# S_M_v4_1_Board.net
KiCad netlist of a schematic drawn in EAGLE
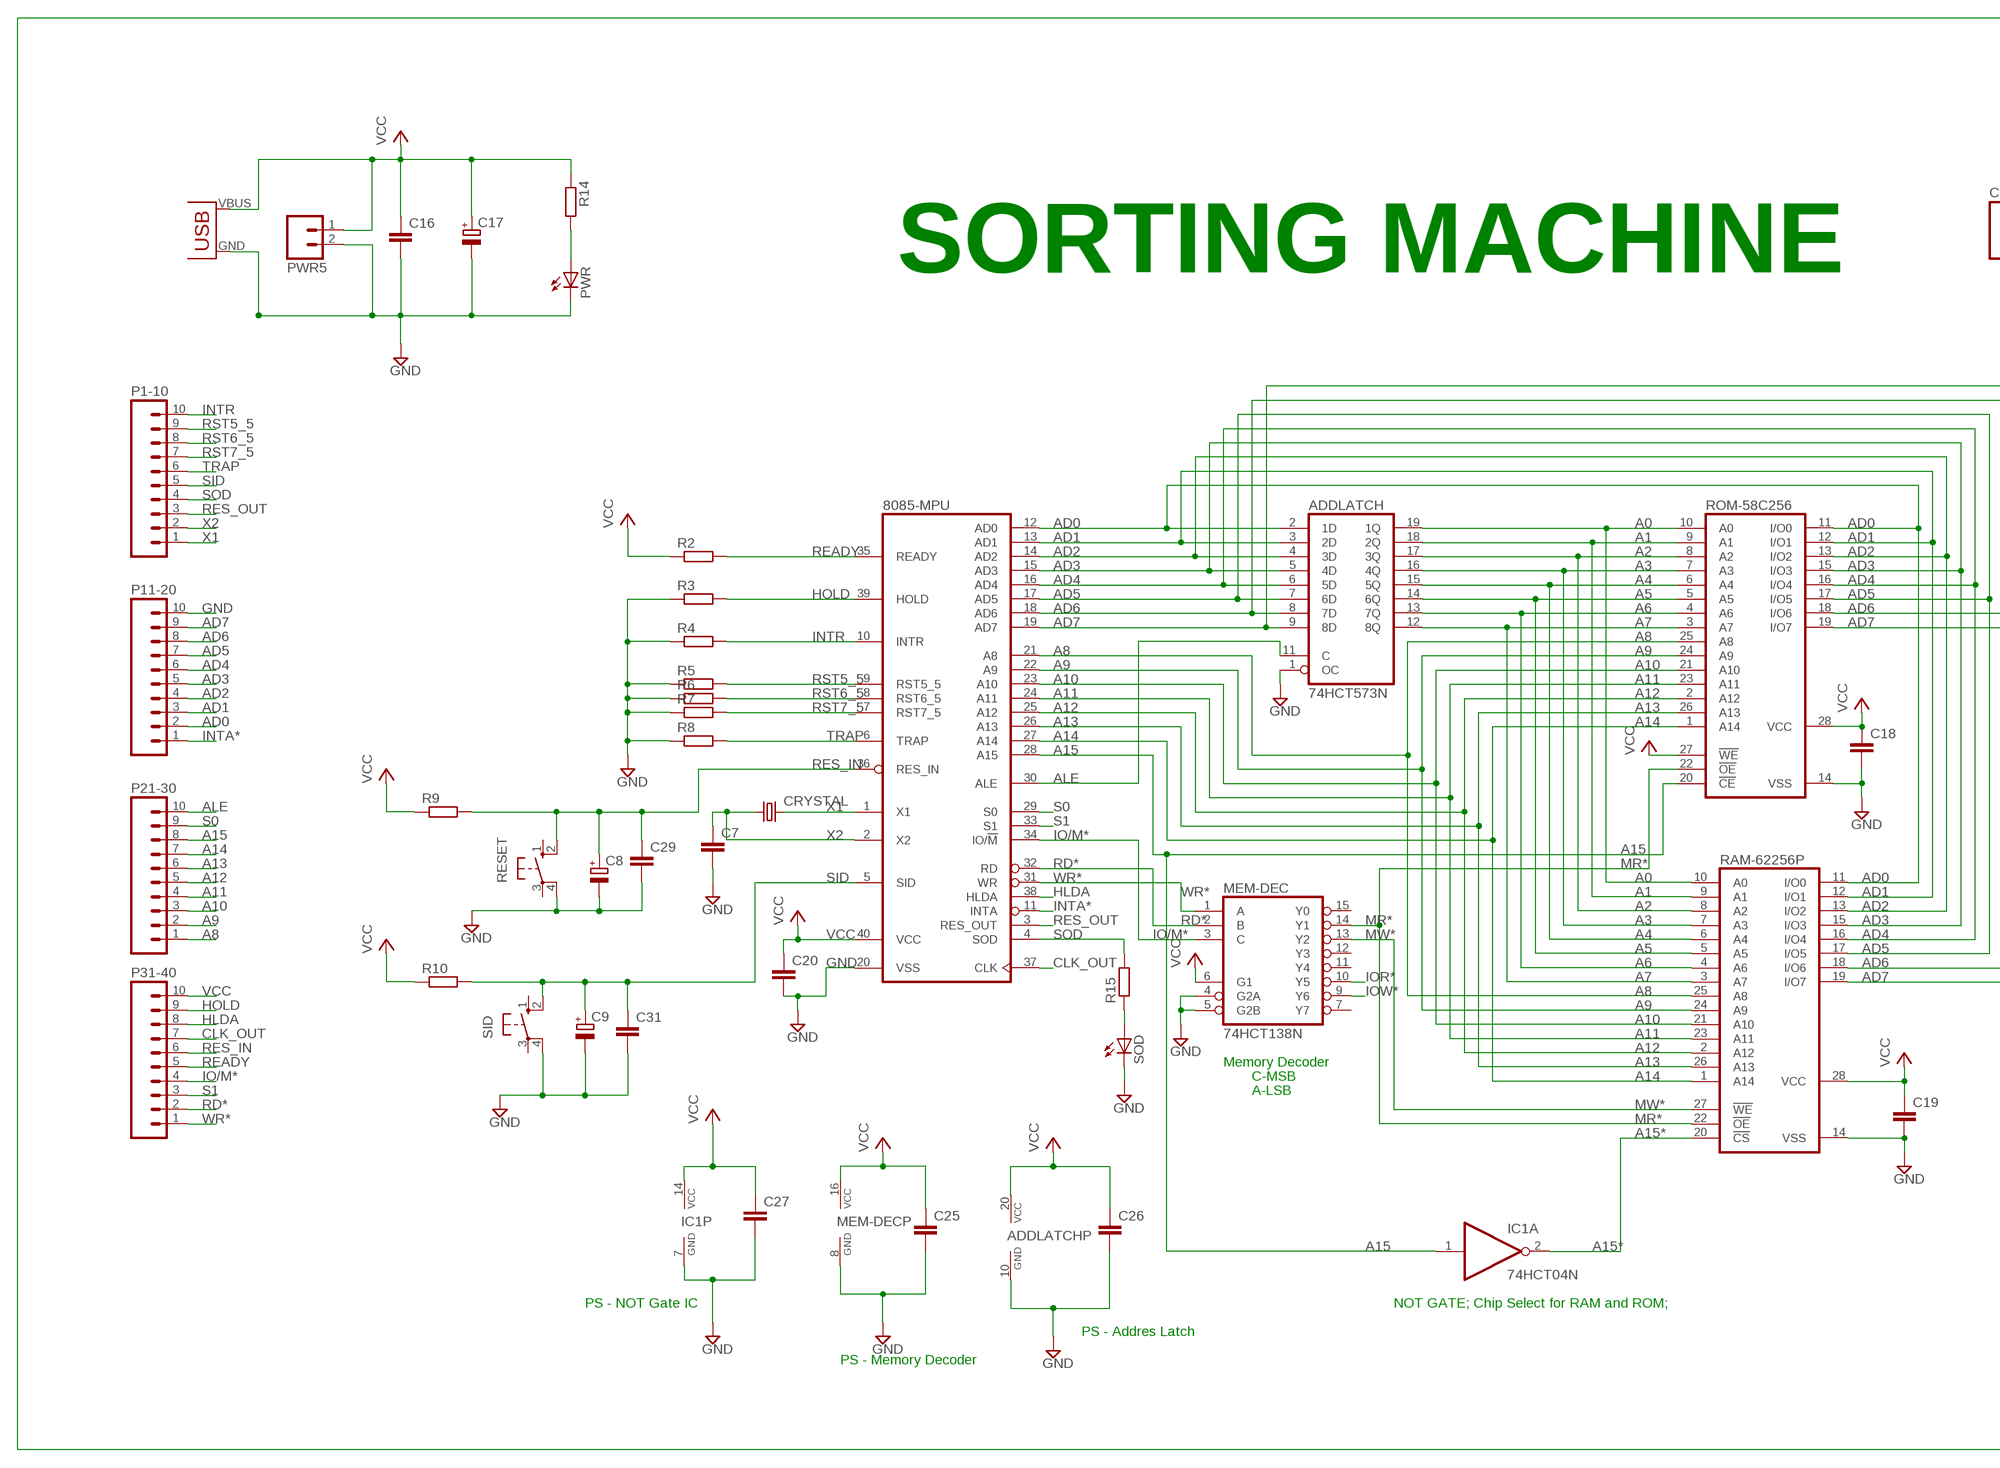
[diagram p0: schematic, sheet 1, part 1 of 2]
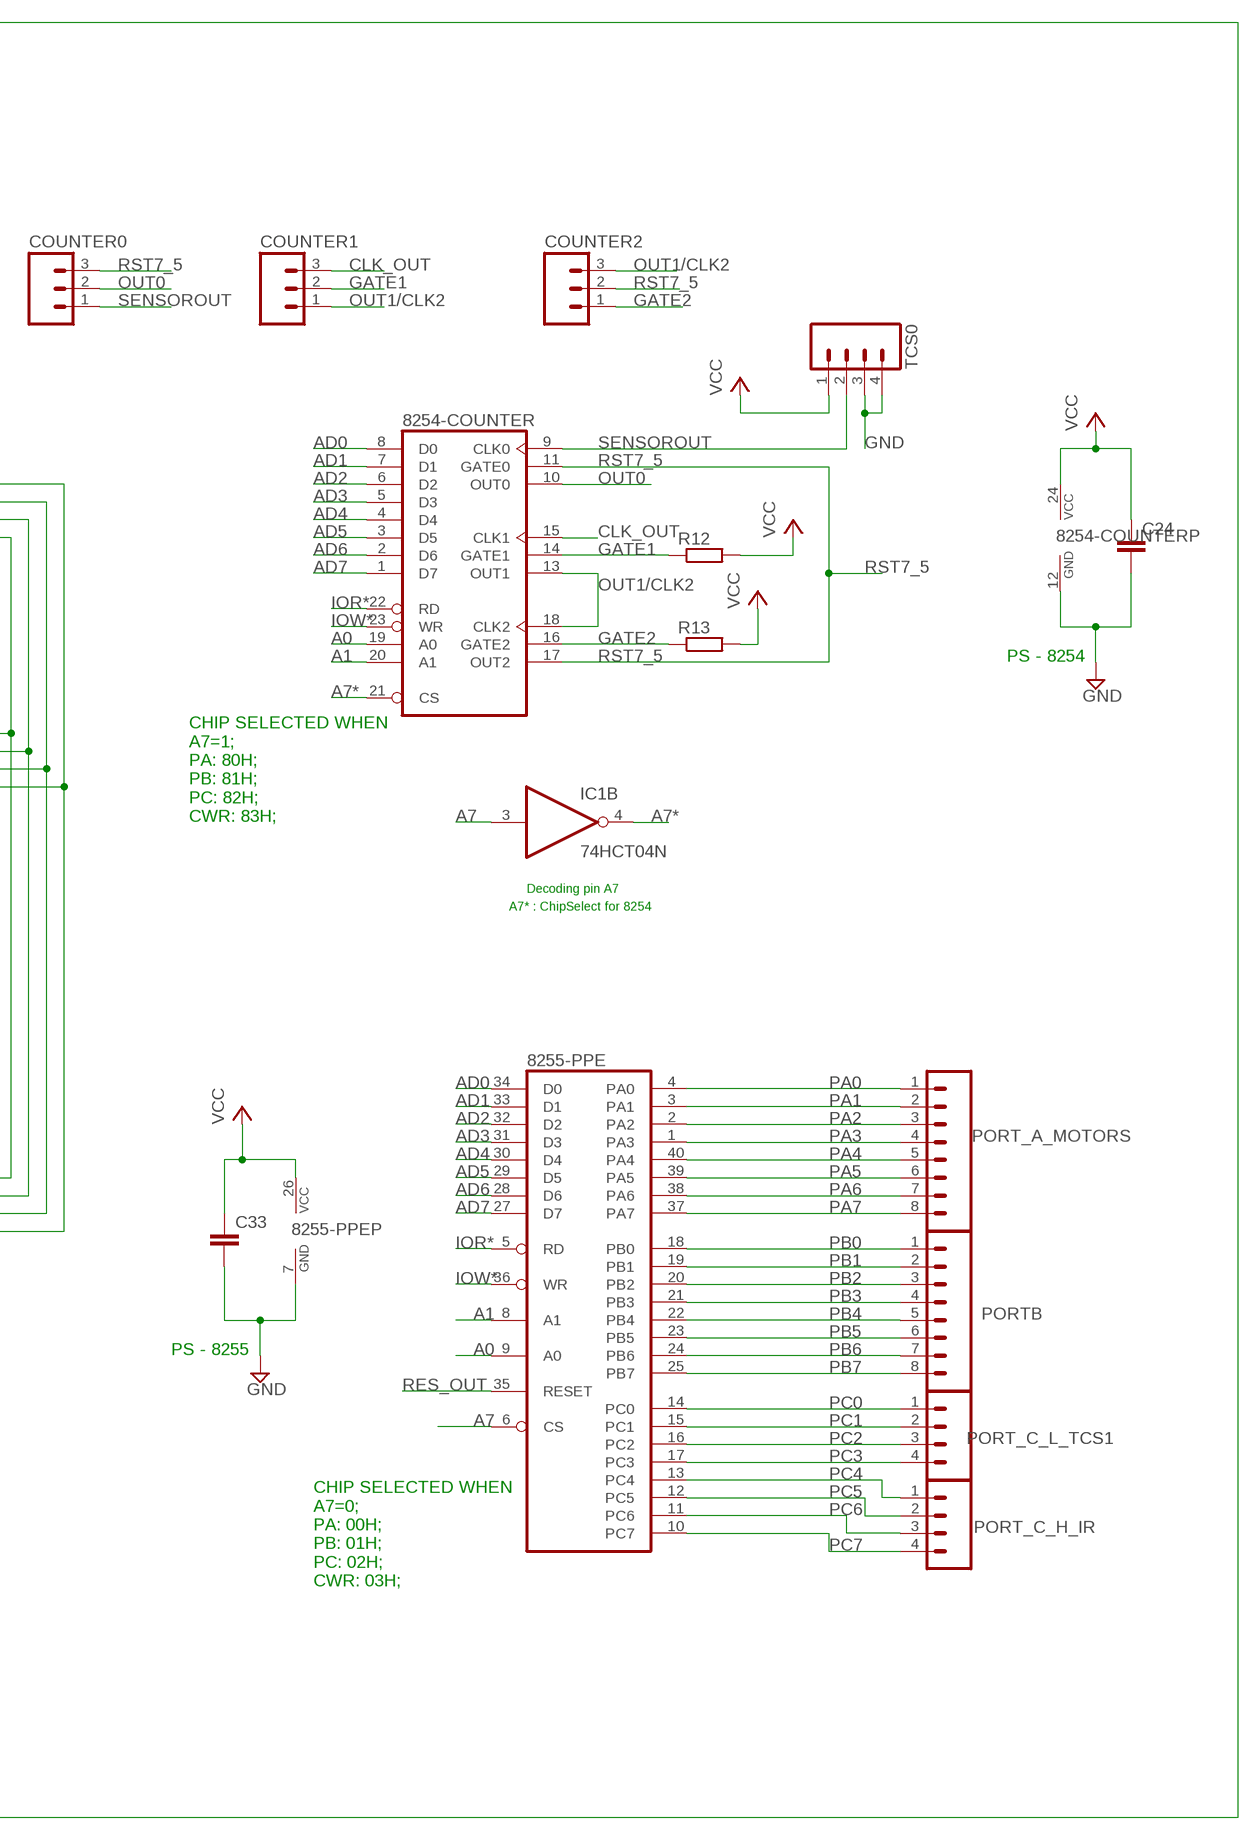
[diagram p1: schematic, sheet 1, part 2 of 2]

(export (version "E")
  (design (tool "Eeschema 10.0.6"))
  (components
    (comp (ref "8085-MPU")
      (value "8085")
      (footprint "eagle-import:DIL40")
      (libsource (lib "eagle-import") (part "8085"))
    )
    (comp (ref "8254-COUNTER")
      (value "8253")
      (footprint "eagle-import:DIL24-6")
      (libsource (lib "eagle-import") (part "8253"))
    )
    (comp (ref "8255-PPE")
      (value "8255A")
      (footprint "eagle-import:DIL40")
      (libsource (lib "eagle-import") (part "8255A"))
    )
    (comp (ref "ADDLATCH")
      (value "74HCT573N")
      (footprint "eagle-import:DIL20")
      (libsource (lib "eagle-import") (part "74573NHCT"))
    )
    (comp (ref "C7")
      (value "C-EU025-025X050")
      (footprint "eagle-import:C025-025X050")
      (libsource (lib "eagle-import") (part "C-EU025-025X050"))
    )
    (comp (ref "C8")
      (value "CPOL-EUE2.5-6")
      (footprint "eagle-import:E2,5-6")
      (libsource (lib "eagle-import") (part "CPOL-EUE2.5-6"))
    )
    (comp (ref "C9")
      (value "CPOL-EUE2.5-6")
      (footprint "eagle-import:E2,5-6")
      (libsource (lib "eagle-import") (part "CPOL-EUE2.5-6"))
    )
    (comp (ref "C16")
      (value "C-EU025-025X050")
      (footprint "eagle-import:C025-025X050")
      (libsource (lib "eagle-import") (part "resistor_C-EU025-025X050"))
    )
    (comp (ref "C17")
      (value "CPOL-EUE2.5-6")
      (footprint "eagle-import:E2,5-6")
      (libsource (lib "eagle-import") (part "CPOL-EUE2.5-6"))
    )
    (comp (ref "C18")
      (value "C-EU025-025X050")
      (footprint "eagle-import:C025-025X050")
      (libsource (lib "eagle-import") (part "resistor_C-EU025-025X050"))
    )
    (comp (ref "C19")
      (value "C-EU025-025X050")
      (footprint "eagle-import:C025-025X050")
      (libsource (lib "eagle-import") (part "resistor_C-EU025-025X050"))
    )
    (comp (ref "C20")
      (value "C-EU025-025X050")
      (footprint "eagle-import:C025-025X050")
      (libsource (lib "eagle-import") (part "resistor_C-EU025-025X050"))
    )
    (comp (ref "C24")
      (value "C-EU025-025X050")
      (footprint "eagle-import:C025-025X050")
      (libsource (lib "eagle-import") (part "resistor_C-EU025-025X050"))
    )
    (comp (ref "C25")
      (value "C-EU025-025X050")
      (footprint "eagle-import:C025-025X050")
      (libsource (lib "eagle-import") (part "resistor_C-EU025-025X050"))
    )
    (comp (ref "C26")
      (value "C-EU025-025X050")
      (footprint "eagle-import:C025-025X050")
      (libsource (lib "eagle-import") (part "resistor_C-EU025-025X050"))
    )
    (comp (ref "C27")
      (value "C-EU025-025X050")
      (footprint "eagle-import:C025-025X050")
      (libsource (lib "eagle-import") (part "resistor_C-EU025-025X050"))
    )
    (comp (ref "C29")
      (value "C-EU025-025X050")
      (footprint "eagle-import:C025-025X050")
      (libsource (lib "eagle-import") (part "C-EU025-025X050"))
    )
    (comp (ref "C31")
      (value "C-EU025-025X050")
      (footprint "eagle-import:C025-025X050")
      (libsource (lib "eagle-import") (part "C-EU025-025X050"))
    )
    (comp (ref "C33")
      (value "C-EU025-025X050")
      (footprint "eagle-import:C025-025X050")
      (libsource (lib "eagle-import") (part "C-EU025-025X050"))
    )
    (comp (ref "COUNTER0")
      (value "M03")
      (footprint "eagle-import:03P")
      (libsource (lib "eagle-import") (part "M03"))
    )
    (comp (ref "COUNTER1")
      (value "M03")
      (footprint "eagle-import:03P")
      (libsource (lib "eagle-import") (part "M03"))
    )
    (comp (ref "COUNTER2")
      (value "M03")
      (footprint "eagle-import:03P")
      (libsource (lib "eagle-import") (part "M03"))
    )
    (comp (ref "CRYSTAL")
      (value "CRYSTALHC49US")
      (footprint "eagle-import:HC49US")
      (libsource (lib "eagle-import") (part "CRYSTALHC49US"))
    )
    (comp (ref "IC1")
      (value "74HCT04N")
      (footprint "eagle-import:DIL14")
      (libsource (lib "eagle-import") (part "7404NHCT"))
    )
    (comp (ref "MEM-DEC")
      (value "74HCT138N")
      (footprint "eagle-import:DIL16")
      (libsource (lib "eagle-import") (part "74138NHCT"))
    )
    (comp (ref "P1-10")
      (value "M10")
      (footprint "eagle-import:10P")
      (libsource (lib "eagle-import") (part "M10"))
    )
    (comp (ref "P11-20")
      (value "M10")
      (footprint "eagle-import:10P")
      (libsource (lib "eagle-import") (part "M10"))
    )
    (comp (ref "P21-30")
      (value "M10")
      (footprint "eagle-import:10P")
      (libsource (lib "eagle-import") (part "M10"))
    )
    (comp (ref "P31-40")
      (value "M10")
      (footprint "eagle-import:10P")
      (libsource (lib "eagle-import") (part "M10"))
    )
    (comp (ref "PORTB")
      (value "M08")
      (footprint "eagle-import:08P")
      (libsource (lib "eagle-import") (part "M08"))
    )
    (comp (ref "PORT_A_MOTORS")
      (value "M08")
      (footprint "eagle-import:08P")
      (libsource (lib "eagle-import") (part "M08"))
    )
    (comp (ref "PORT_C_H_IR")
      (value "M04")
      (footprint "eagle-import:04P")
      (libsource (lib "eagle-import") (part "M04"))
    )
    (comp (ref "PORT_C_L_TCS1")
      (value "M04")
      (footprint "eagle-import:04P")
      (libsource (lib "eagle-import") (part "M04"))
    )
    (comp (ref "PWR")
      (value "LED5MM")
      (footprint "eagle-import:LED5MM")
      (libsource (lib "eagle-import") (part "LED5MM"))
    )
    (comp (ref "PWR5")
      (value "M02")
      (footprint "eagle-import:02P")
      (libsource (lib "eagle-import") (part "M02"))
    )
    (comp (ref "R2")
      (value "R-EU_0204/7")
      (footprint "eagle-import:0204_7")
      (libsource (lib "eagle-import") (part "R-EU_0204/7"))
    )
    (comp (ref "R3")
      (value "R-EU_0204/7")
      (footprint "eagle-import:0204_7")
      (libsource (lib "eagle-import") (part "R-EU_0204/7"))
    )
    (comp (ref "R4")
      (value "R-EU_0204/7")
      (footprint "eagle-import:0204_7")
      (libsource (lib "eagle-import") (part "R-EU_0204/7"))
    )
    (comp (ref "R5")
      (value "R-EU_0204/7")
      (footprint "eagle-import:0204_7")
      (libsource (lib "eagle-import") (part "R-EU_0204/7"))
    )
    (comp (ref "R6")
      (value "R-EU_0204/7")
      (footprint "eagle-import:0204_7")
      (libsource (lib "eagle-import") (part "R-EU_0204/7"))
    )
    (comp (ref "R7")
      (value "R-EU_0204/7")
      (footprint "eagle-import:0204_7")
      (libsource (lib "eagle-import") (part "R-EU_0204/7"))
    )
    (comp (ref "R8")
      (value "R-EU_0204/7")
      (footprint "eagle-import:0204_7")
      (libsource (lib "eagle-import") (part "R-EU_0204/7"))
    )
    (comp (ref "R9")
      (value "R-EU_0204/7")
      (footprint "eagle-import:0204_7")
      (libsource (lib "eagle-import") (part "resistor_R-EU_0204/7"))
    )
    (comp (ref "R10")
      (value "R-EU_0204/7")
      (footprint "eagle-import:0204_7")
      (libsource (lib "eagle-import") (part "resistor_R-EU_0204/7"))
    )
    (comp (ref "R12")
      (value "R-EU_0204/7")
      (footprint "eagle-import:0204_7")
      (libsource (lib "eagle-import") (part "R-EU_0204/7"))
    )
    (comp (ref "R13")
      (value "R-EU_0204/7")
      (footprint "eagle-import:0204_7")
      (libsource (lib "eagle-import") (part "R-EU_0204/7"))
    )
    (comp (ref "R14")
      (value "R-EU_0204/7")
      (footprint "eagle-import:0204_7")
      (libsource (lib "eagle-import") (part "R-EU_0204/7"))
    )
    (comp (ref "R15")
      (value "R-EU_0204/7")
      (footprint "eagle-import:0204_7")
      (libsource (lib "eagle-import") (part "R-EU_0204/7"))
    )
    (comp (ref "RAM-62256P")
      (value "62256P")
      (footprint "eagle-import:DIL28-6")
      (libsource (lib "eagle-import") (part "62256P"))
    )
    (comp (ref "RESET")
      (value "10-XX")
      (footprint "eagle-import:B3F-10XX")
      (fields (field (name "MPN") "B3F-1000"))
      (libsource (lib "eagle-import") (part "10-XX"))
    )
    (comp (ref "ROM-58C256")
      (value "58C256P")
      (footprint "eagle-import:DIL28-6")
      (fields (field (name "MPN") "HN58C256AP85E"))
      (libsource (lib "eagle-import") (part "58C256P"))
    )
    (comp (ref "SID")
      (value "10-XX")
      (footprint "eagle-import:B3F-10XX")
      (fields (field (name "MPN") "B3F-1000"))
      (libsource (lib "eagle-import") (part "10-XX"))
    )
    (comp (ref "SOD")
      (value "LED5MM")
      (footprint "eagle-import:LED5MM")
      (libsource (lib "eagle-import") (part "LED5MM"))
    )
    (comp (ref "TCS0")
      (value "M04")
      (footprint "eagle-import:04P")
      (libsource (lib "eagle-import") (part "M04"))
    )
    (comp (ref "USB")
      (value "USB(POWER)")
      (footprint "eagle-import:USB(POWER)")
      (libsource (lib "eagle-import") (part "USB(POWER)"))
    )
  )
  (nets
    (net (code "1") (name "/A0") (class "Default")
      (node (ref "8254-COUNTER") (pin "19") (pinfunction "A0_19") (pintype "input"))
      (node (ref "8255-PPE") (pin "9") (pinfunction "A0_9") (pintype "input"))
      (node (ref "ADDLATCH") (pin "19") (pinfunction "1Q_19") (pintype "tri_state"))
      (node (ref "RAM-62256P") (pin "10") (pinfunction "A0_10") (pintype "input"))
      (node (ref "ROM-58C256") (pin "10") (pinfunction "A0_10") (pintype "input"))
    )
    (net (code "2") (name "/A1") (class "Default")
      (node (ref "8254-COUNTER") (pin "20") (pinfunction "A1_20") (pintype "input"))
      (node (ref "8255-PPE") (pin "8") (pinfunction "A1_8") (pintype "input"))
      (node (ref "ADDLATCH") (pin "18") (pinfunction "2Q_18") (pintype "tri_state"))
      (node (ref "RAM-62256P") (pin "9") (pinfunction "A1_9") (pintype "input"))
      (node (ref "ROM-58C256") (pin "9") (pinfunction "A1_9") (pintype "input"))
    )
    (net (code "3") (name "/A2") (class "Default")
      (node (ref "ADDLATCH") (pin "17") (pinfunction "3Q_17") (pintype "tri_state"))
      (node (ref "RAM-62256P") (pin "8") (pinfunction "A2_8") (pintype "input"))
      (node (ref "ROM-58C256") (pin "8") (pinfunction "A2_8") (pintype "input"))
    )
    (net (code "4") (name "/A3") (class "Default")
      (node (ref "ADDLATCH") (pin "16") (pinfunction "4Q_16") (pintype "tri_state"))
      (node (ref "RAM-62256P") (pin "7") (pinfunction "A3_7") (pintype "input"))
      (node (ref "ROM-58C256") (pin "7") (pinfunction "A3_7") (pintype "input"))
    )
    (net (code "5") (name "/A4") (class "Default")
      (node (ref "ADDLATCH") (pin "15") (pinfunction "5Q_15") (pintype "tri_state"))
      (node (ref "RAM-62256P") (pin "6") (pinfunction "A4_6") (pintype "input"))
      (node (ref "ROM-58C256") (pin "6") (pinfunction "A4_6") (pintype "input"))
    )
    (net (code "6") (name "/A5") (class "Default")
      (node (ref "ADDLATCH") (pin "14") (pinfunction "6Q_14") (pintype "tri_state"))
      (node (ref "RAM-62256P") (pin "5") (pinfunction "A5_5") (pintype "input"))
      (node (ref "ROM-58C256") (pin "5") (pinfunction "A5_5") (pintype "input"))
    )
    (net (code "7") (name "/A6") (class "Default")
      (node (ref "ADDLATCH") (pin "13") (pinfunction "7Q_13") (pintype "tri_state"))
      (node (ref "RAM-62256P") (pin "4") (pinfunction "A6_4") (pintype "input"))
      (node (ref "ROM-58C256") (pin "4") (pinfunction "A6_4") (pintype "input"))
    )
    (net (code "8") (name "/A7") (class "Default")
      (node (ref "8255-PPE") (pin "6") (pinfunction "CS_6") (pintype "input"))
      (node (ref "ADDLATCH") (pin "12") (pinfunction "8Q_12") (pintype "tri_state"))
      (node (ref "IC1") (pin "3") (pinfunction "I_3") (pintype "input"))
      (node (ref "RAM-62256P") (pin "3") (pinfunction "A7_3") (pintype "input"))
      (node (ref "ROM-58C256") (pin "3") (pinfunction "A7_3") (pintype "input"))
    )
    (net (code "9") (name "/A7*") (class "Default")
      (node (ref "8254-COUNTER") (pin "21") (pinfunction "CS_21") (pintype "input"))
      (node (ref "IC1") (pin "4") (pinfunction "O_4") (pintype "output"))
    )
    (net (code "10") (name "/A8") (class "Default")
      (node (ref "8085-MPU") (pin "21") (pinfunction "A8_21") (pintype "output"))
      (node (ref "P21-30") (pin "1") (pinfunction "1_1") (pintype "passive"))
      (node (ref "RAM-62256P") (pin "25") (pinfunction "A8_25") (pintype "input"))
      (node (ref "ROM-58C256") (pin "25") (pinfunction "A8_25") (pintype "input"))
    )
    (net (code "11") (name "/A9") (class "Default")
      (node (ref "8085-MPU") (pin "22") (pinfunction "A9_22") (pintype "output"))
      (node (ref "P21-30") (pin "2") (pinfunction "2_2") (pintype "passive"))
      (node (ref "RAM-62256P") (pin "24") (pinfunction "A9_24") (pintype "input"))
      (node (ref "ROM-58C256") (pin "24") (pinfunction "A9_24") (pintype "input"))
    )
    (net (code "12") (name "/A10") (class "Default")
      (node (ref "8085-MPU") (pin "23") (pinfunction "A10_23") (pintype "output"))
      (node (ref "P21-30") (pin "3") (pinfunction "3_3") (pintype "passive"))
      (node (ref "RAM-62256P") (pin "21") (pinfunction "A10_21") (pintype "input"))
      (node (ref "ROM-58C256") (pin "21") (pinfunction "A10_21") (pintype "input"))
    )
    (net (code "13") (name "/A11") (class "Default")
      (node (ref "8085-MPU") (pin "24") (pinfunction "A11_24") (pintype "output"))
      (node (ref "P21-30") (pin "4") (pinfunction "4_4") (pintype "passive"))
      (node (ref "RAM-62256P") (pin "23") (pinfunction "A11_23") (pintype "input"))
      (node (ref "ROM-58C256") (pin "23") (pinfunction "A11_23") (pintype "input"))
    )
    (net (code "14") (name "/A12") (class "Default")
      (node (ref "8085-MPU") (pin "25") (pinfunction "A12_25") (pintype "output"))
      (node (ref "P21-30") (pin "5") (pinfunction "5_5") (pintype "passive"))
      (node (ref "RAM-62256P") (pin "2") (pinfunction "A12_2") (pintype "input"))
      (node (ref "ROM-58C256") (pin "2") (pinfunction "A12_2") (pintype "input"))
    )
    (net (code "15") (name "/A13") (class "Default")
      (node (ref "8085-MPU") (pin "26") (pinfunction "A13_26") (pintype "output"))
      (node (ref "P21-30") (pin "6") (pinfunction "6_6") (pintype "passive"))
      (node (ref "RAM-62256P") (pin "26") (pinfunction "A13_26") (pintype "input"))
      (node (ref "ROM-58C256") (pin "26") (pinfunction "A13_26") (pintype "input"))
    )
    (net (code "16") (name "/A14") (class "Default")
      (node (ref "8085-MPU") (pin "27") (pinfunction "A14_27") (pintype "output"))
      (node (ref "P21-30") (pin "7") (pinfunction "7_7") (pintype "passive"))
      (node (ref "RAM-62256P") (pin "1") (pinfunction "A14_1") (pintype "input"))
      (node (ref "ROM-58C256") (pin "1") (pinfunction "A14_1") (pintype "input"))
    )
    (net (code "17") (name "/A15") (class "Default")
      (node (ref "8085-MPU") (pin "28") (pinfunction "A15_28") (pintype "output"))
      (node (ref "IC1") (pin "1") (pinfunction "I_1") (pintype "input"))
      (node (ref "P21-30") (pin "8") (pinfunction "8_8") (pintype "passive"))
      (node (ref "ROM-58C256") (pin "20") (pinfunction "~{CE}_20") (pintype "input"))
    )
    (net (code "18") (name "/A15*") (class "Default")
      (node (ref "IC1") (pin "2") (pinfunction "O_2") (pintype "output"))
      (node (ref "RAM-62256P") (pin "20") (pinfunction "~{CS}_20") (pintype "input"))
    )
    (net (code "19") (name "/AD0") (class "Default")
      (node (ref "8085-MPU") (pin "12") (pinfunction "AD0_12") (pintype "bidirectional"))
      (node (ref "8254-COUNTER") (pin "8") (pinfunction "D0_8") (pintype "bidirectional"))
      (node (ref "8255-PPE") (pin "34") (pinfunction "D0_34") (pintype "bidirectional"))
      (node (ref "ADDLATCH") (pin "2") (pinfunction "1D_2") (pintype "input"))
      (node (ref "P11-20") (pin "2") (pinfunction "2_2") (pintype "passive"))
      (node (ref "RAM-62256P") (pin "11") (pinfunction "I/O0_11") (pintype "bidirectional"))
      (node (ref "ROM-58C256") (pin "11") (pinfunction "I/O0_11") (pintype "tri_state"))
    )
    (net (code "20") (name "/AD1") (class "Default")
      (node (ref "8085-MPU") (pin "13") (pinfunction "AD1_13") (pintype "bidirectional"))
      (node (ref "8254-COUNTER") (pin "7") (pinfunction "D1_7") (pintype "bidirectional"))
      (node (ref "8255-PPE") (pin "33") (pinfunction "D1_33") (pintype "bidirectional"))
      (node (ref "ADDLATCH") (pin "3") (pinfunction "2D_3") (pintype "input"))
      (node (ref "P11-20") (pin "3") (pinfunction "3_3") (pintype "passive"))
      (node (ref "RAM-62256P") (pin "12") (pinfunction "I/O1_12") (pintype "bidirectional"))
      (node (ref "ROM-58C256") (pin "12") (pinfunction "I/O1_12") (pintype "tri_state"))
    )
    (net (code "21") (name "/AD2") (class "Default")
      (node (ref "8085-MPU") (pin "14") (pinfunction "AD2_14") (pintype "bidirectional"))
      (node (ref "8254-COUNTER") (pin "6") (pinfunction "D2_6") (pintype "bidirectional"))
      (node (ref "8255-PPE") (pin "32") (pinfunction "D2_32") (pintype "bidirectional"))
      (node (ref "ADDLATCH") (pin "4") (pinfunction "3D_4") (pintype "input"))
      (node (ref "P11-20") (pin "4") (pinfunction "4_4") (pintype "passive"))
      (node (ref "RAM-62256P") (pin "13") (pinfunction "I/O2_13") (pintype "bidirectional"))
      (node (ref "ROM-58C256") (pin "13") (pinfunction "I/O2_13") (pintype "tri_state"))
    )
    (net (code "22") (name "/AD3") (class "Default")
      (node (ref "8085-MPU") (pin "15") (pinfunction "AD3_15") (pintype "bidirectional"))
      (node (ref "8254-COUNTER") (pin "5") (pinfunction "D3_5") (pintype "bidirectional"))
      (node (ref "8255-PPE") (pin "31") (pinfunction "D3_31") (pintype "bidirectional"))
      (node (ref "ADDLATCH") (pin "5") (pinfunction "4D_5") (pintype "input"))
      (node (ref "P11-20") (pin "5") (pinfunction "5_5") (pintype "passive"))
      (node (ref "RAM-62256P") (pin "15") (pinfunction "I/O3_15") (pintype "bidirectional"))
      (node (ref "ROM-58C256") (pin "15") (pinfunction "I/O3_15") (pintype "tri_state"))
    )
    (net (code "23") (name "/AD4") (class "Default")
      (node (ref "8085-MPU") (pin "16") (pinfunction "AD4_16") (pintype "bidirectional"))
      (node (ref "8254-COUNTER") (pin "4") (pinfunction "D4_4") (pintype "bidirectional"))
      (node (ref "8255-PPE") (pin "30") (pinfunction "D4_30") (pintype "bidirectional"))
      (node (ref "ADDLATCH") (pin "6") (pinfunction "5D_6") (pintype "input"))
      (node (ref "P11-20") (pin "6") (pinfunction "6_6") (pintype "passive"))
      (node (ref "RAM-62256P") (pin "16") (pinfunction "I/O4_16") (pintype "bidirectional"))
      (node (ref "ROM-58C256") (pin "16") (pinfunction "I/O4_16") (pintype "tri_state"))
    )
    (net (code "24") (name "/AD5") (class "Default")
      (node (ref "8085-MPU") (pin "17") (pinfunction "AD5_17") (pintype "bidirectional"))
      (node (ref "8254-COUNTER") (pin "3") (pinfunction "D5_3") (pintype "bidirectional"))
      (node (ref "8255-PPE") (pin "29") (pinfunction "D5_29") (pintype "bidirectional"))
      (node (ref "ADDLATCH") (pin "7") (pinfunction "6D_7") (pintype "input"))
      (node (ref "P11-20") (pin "7") (pinfunction "7_7") (pintype "passive"))
      (node (ref "RAM-62256P") (pin "17") (pinfunction "I/O5_17") (pintype "bidirectional"))
      (node (ref "ROM-58C256") (pin "17") (pinfunction "I/O5_17") (pintype "tri_state"))
    )
    (net (code "25") (name "/AD6") (class "Default")
      (node (ref "8085-MPU") (pin "18") (pinfunction "AD6_18") (pintype "bidirectional"))
      (node (ref "8254-COUNTER") (pin "2") (pinfunction "D6_2") (pintype "bidirectional"))
      (node (ref "8255-PPE") (pin "28") (pinfunction "D6_28") (pintype "bidirectional"))
      (node (ref "ADDLATCH") (pin "8") (pinfunction "7D_8") (pintype "input"))
      (node (ref "P11-20") (pin "8") (pinfunction "8_8") (pintype "passive"))
      (node (ref "RAM-62256P") (pin "18") (pinfunction "I/O6_18") (pintype "bidirectional"))
      (node (ref "ROM-58C256") (pin "18") (pinfunction "I/O6_18") (pintype "tri_state"))
    )
    (net (code "26") (name "/AD7") (class "Default")
      (node (ref "8085-MPU") (pin "19") (pinfunction "AD7_19") (pintype "bidirectional"))
      (node (ref "8254-COUNTER") (pin "1") (pinfunction "D7_1") (pintype "bidirectional"))
      (node (ref "8255-PPE") (pin "27") (pinfunction "D7_27") (pintype "bidirectional"))
      (node (ref "ADDLATCH") (pin "9") (pinfunction "8D_9") (pintype "input"))
      (node (ref "P11-20") (pin "9") (pinfunction "9_9") (pintype "passive"))
      (node (ref "RAM-62256P") (pin "19") (pinfunction "I/O7_19") (pintype "bidirectional"))
      (node (ref "ROM-58C256") (pin "19") (pinfunction "I/O7_19") (pintype "tri_state"))
    )
    (net (code "27") (name "/ALE") (class "Default")
      (node (ref "8085-MPU") (pin "30") (pinfunction "ALE_30") (pintype "output"))
      (node (ref "ADDLATCH") (pin "11") (pinfunction "C_11") (pintype "input"))
      (node (ref "P21-30") (pin "10") (pinfunction "10_10") (pintype "passive"))
    )
    (net (code "28") (name "/CLK_OUT") (class "Default")
      (node (ref "8085-MPU") (pin "37") (pinfunction "CLK_37") (pintype "output"))
      (node (ref "8254-COUNTER") (pin "15") (pinfunction "CLK1_15") (pintype "input"))
      (node (ref "COUNTER1") (pin "3") (pinfunction "3_3") (pintype "passive"))
      (node (ref "P31-40") (pin "7") (pinfunction "7_7") (pintype "passive"))
    )
    (net (code "29") (name "/GATE1") (class "Default")
      (node (ref "8254-COUNTER") (pin "14") (pinfunction "GATE1_14") (pintype "input"))
      (node (ref "COUNTER1") (pin "2") (pinfunction "2_2") (pintype "passive"))
      (node (ref "R12") (pin "1") (pinfunction "1_1") (pintype "passive"))
    )
    (net (code "30") (name "/GATE2") (class "Default")
      (node (ref "8254-COUNTER") (pin "16") (pinfunction "GATE2_16") (pintype "input"))
      (node (ref "COUNTER2") (pin "1") (pinfunction "1_1") (pintype "passive"))
      (node (ref "R13") (pin "1") (pinfunction "1_1") (pintype "passive"))
    )
    (net (code "31") (name "/HLDA") (class "Default")
      (node (ref "8085-MPU") (pin "38") (pinfunction "HLDA_38") (pintype "output"))
      (node (ref "P31-40") (pin "8") (pinfunction "8_8") (pintype "passive"))
    )
    (net (code "32") (name "/HOLD") (class "Default")
      (node (ref "8085-MPU") (pin "39") (pinfunction "HOLD_39") (pintype "input"))
      (node (ref "P31-40") (pin "9") (pinfunction "9_9") (pintype "passive"))
      (node (ref "R3") (pin "2") (pinfunction "2_2") (pintype "passive"))
    )
    (net (code "33") (name "/INTA*") (class "Default")
      (node (ref "8085-MPU") (pin "11") (pinfunction "INTA_11") (pintype "output"))
      (node (ref "P11-20") (pin "1") (pinfunction "1_1") (pintype "passive"))
    )
    (net (code "34") (name "/INTR") (class "Default")
      (node (ref "8085-MPU") (pin "10") (pinfunction "INTR_10") (pintype "input"))
      (node (ref "P1-10") (pin "10") (pinfunction "10_10") (pintype "passive"))
      (node (ref "R4") (pin "2") (pinfunction "2_2") (pintype "passive"))
    )
    (net (code "35") (name "/IOR*") (class "Default")
      (node (ref "8254-COUNTER") (pin "22") (pinfunction "RD_22") (pintype "input"))
      (node (ref "8255-PPE") (pin "5") (pinfunction "RD_5") (pintype "input"))
      (node (ref "MEM-DEC") (pin "10") (pinfunction "Y5_10") (pintype "output"))
    )
    (net (code "36") (name "/IOW*") (class "Default")
      (node (ref "8254-COUNTER") (pin "23") (pinfunction "WR_23") (pintype "input"))
      (node (ref "8255-PPE") (pin "36") (pinfunction "WR_36") (pintype "input"))
      (node (ref "MEM-DEC") (pin "9") (pinfunction "Y6_9") (pintype "output"))
    )
    (net (code "37") (name "/IO{slash}M*") (class "Default")
      (node (ref "8085-MPU") (pin "34") (pinfunction "IO/~{M}_34") (pintype "output"))
      (node (ref "MEM-DEC") (pin "3") (pinfunction "C_3") (pintype "input"))
      (node (ref "P31-40") (pin "4") (pinfunction "4_4") (pintype "passive"))
    )
    (net (code "38") (name "/MR*") (class "Default")
      (node (ref "MEM-DEC") (pin "14") (pinfunction "Y1_14") (pintype "output"))
      (node (ref "RAM-62256P") (pin "22") (pinfunction "~{OE}_22") (pintype "input"))
      (node (ref "ROM-58C256") (pin "22") (pinfunction "~{OE}_22") (pintype "input"))
    )
    (net (code "39") (name "/MW*") (class "Default")
      (node (ref "MEM-DEC") (pin "13") (pinfunction "Y2_13") (pintype "output"))
      (node (ref "RAM-62256P") (pin "27") (pinfunction "~{WE}_27") (pintype "input"))
    )
    (net (code "40") (name "/OUT0") (class "Default")
      (node (ref "8254-COUNTER") (pin "10") (pinfunction "OUT0_10") (pintype "output"))
      (node (ref "COUNTER0") (pin "2") (pinfunction "2_2") (pintype "passive"))
    )
    (net (code "41") (name "/OUT1{slash}CLK2") (class "Default")
      (node (ref "8254-COUNTER") (pin "13") (pinfunction "OUT1_13") (pintype "output"))
      (node (ref "8254-COUNTER") (pin "18") (pinfunction "CLK2_18") (pintype "input"))
      (node (ref "COUNTER1") (pin "1") (pinfunction "1_1") (pintype "passive"))
      (node (ref "COUNTER2") (pin "3") (pinfunction "3_3") (pintype "passive"))
    )
    (net (code "42") (name "/PA0") (class "Default")
      (node (ref "8255-PPE") (pin "4") (pinfunction "PA0_4") (pintype "bidirectional"))
      (node (ref "PORT_A_MOTORS") (pin "1") (pinfunction "1_1") (pintype "passive"))
    )
    (net (code "43") (name "/PA1") (class "Default")
      (node (ref "8255-PPE") (pin "3") (pinfunction "PA1_3") (pintype "bidirectional"))
      (node (ref "PORT_A_MOTORS") (pin "2") (pinfunction "2_2") (pintype "passive"))
    )
    (net (code "44") (name "/PA2") (class "Default")
      (node (ref "8255-PPE") (pin "2") (pinfunction "PA2_2") (pintype "bidirectional"))
      (node (ref "PORT_A_MOTORS") (pin "3") (pinfunction "3_3") (pintype "passive"))
    )
    (net (code "45") (name "/PA3") (class "Default")
      (node (ref "8255-PPE") (pin "1") (pinfunction "PA3_1") (pintype "bidirectional"))
      (node (ref "PORT_A_MOTORS") (pin "4") (pinfunction "4_4") (pintype "passive"))
    )
    (net (code "46") (name "/PA4") (class "Default")
      (node (ref "8255-PPE") (pin "40") (pinfunction "PA4_40") (pintype "bidirectional"))
      (node (ref "PORT_A_MOTORS") (pin "5") (pinfunction "5_5") (pintype "passive"))
    )
    (net (code "47") (name "/PA5") (class "Default")
      (node (ref "8255-PPE") (pin "39") (pinfunction "PA5_39") (pintype "bidirectional"))
      (node (ref "PORT_A_MOTORS") (pin "6") (pinfunction "6_6") (pintype "passive"))
    )
    (net (code "48") (name "/PA6") (class "Default")
      (node (ref "8255-PPE") (pin "38") (pinfunction "PA6_38") (pintype "bidirectional"))
      (node (ref "PORT_A_MOTORS") (pin "7") (pinfunction "7_7") (pintype "passive"))
    )
    (net (code "49") (name "/PA7") (class "Default")
      (node (ref "8255-PPE") (pin "37") (pinfunction "PA7_37") (pintype "bidirectional"))
      (node (ref "PORT_A_MOTORS") (pin "8") (pinfunction "8_8") (pintype "passive"))
    )
    (net (code "50") (name "/PB0") (class "Default")
      (node (ref "8255-PPE") (pin "18") (pinfunction "PB0_18") (pintype "bidirectional"))
      (node (ref "PORTB") (pin "1") (pinfunction "1_1") (pintype "passive"))
    )
    (net (code "51") (name "/PB1") (class "Default")
      (node (ref "8255-PPE") (pin "19") (pinfunction "PB1_19") (pintype "bidirectional"))
      (node (ref "PORTB") (pin "2") (pinfunction "2_2") (pintype "passive"))
    )
    (net (code "52") (name "/PB2") (class "Default")
      (node (ref "8255-PPE") (pin "20") (pinfunction "PB2_20") (pintype "bidirectional"))
      (node (ref "PORTB") (pin "3") (pinfunction "3_3") (pintype "passive"))
    )
    (net (code "53") (name "/PB3") (class "Default")
      (node (ref "8255-PPE") (pin "21") (pinfunction "PB3_21") (pintype "bidirectional"))
      (node (ref "PORTB") (pin "4") (pinfunction "4_4") (pintype "passive"))
    )
    (net (code "54") (name "/PB4") (class "Default")
      (node (ref "8255-PPE") (pin "22") (pinfunction "PB4_22") (pintype "bidirectional"))
      (node (ref "PORTB") (pin "5") (pinfunction "5_5") (pintype "passive"))
    )
    (net (code "55") (name "/PB5") (class "Default")
      (node (ref "8255-PPE") (pin "23") (pinfunction "PB5_23") (pintype "bidirectional"))
      (node (ref "PORTB") (pin "6") (pinfunction "6_6") (pintype "passive"))
    )
    (net (code "56") (name "/PB6") (class "Default")
      (node (ref "8255-PPE") (pin "24") (pinfunction "PB6_24") (pintype "bidirectional"))
      (node (ref "PORTB") (pin "7") (pinfunction "7_7") (pintype "passive"))
    )
    (net (code "57") (name "/PB7") (class "Default")
      (node (ref "8255-PPE") (pin "25") (pinfunction "PB7_25") (pintype "bidirectional"))
      (node (ref "PORTB") (pin "8") (pinfunction "8_8") (pintype "passive"))
    )
    (net (code "58") (name "/PC0") (class "Default")
      (node (ref "8255-PPE") (pin "14") (pinfunction "PC0_14") (pintype "bidirectional"))
      (node (ref "PORT_C_L_TCS1") (pin "1") (pinfunction "1_1") (pintype "passive"))
    )
    (net (code "59") (name "/PC1") (class "Default")
      (node (ref "8255-PPE") (pin "15") (pinfunction "PC1_15") (pintype "bidirectional"))
      (node (ref "PORT_C_L_TCS1") (pin "2") (pinfunction "2_2") (pintype "passive"))
    )
    (net (code "60") (name "/PC2") (class "Default")
      (node (ref "8255-PPE") (pin "16") (pinfunction "PC2_16") (pintype "bidirectional"))
      (node (ref "PORT_C_L_TCS1") (pin "3") (pinfunction "3_3") (pintype "passive"))
    )
    (net (code "61") (name "/PC3") (class "Default")
      (node (ref "8255-PPE") (pin "17") (pinfunction "PC3_17") (pintype "bidirectional"))
      (node (ref "PORT_C_L_TCS1") (pin "4") (pinfunction "4_4") (pintype "passive"))
    )
    (net (code "62") (name "/PC4") (class "Default")
      (node (ref "8255-PPE") (pin "13") (pinfunction "PC4_13") (pintype "bidirectional"))
      (node (ref "PORT_C_H_IR") (pin "1") (pinfunction "1_1") (pintype "passive"))
    )
    (net (code "63") (name "/PC5") (class "Default")
      (node (ref "8255-PPE") (pin "12") (pinfunction "PC5_12") (pintype "bidirectional"))
      (node (ref "PORT_C_H_IR") (pin "2") (pinfunction "2_2") (pintype "passive"))
    )
    (net (code "64") (name "/PC6") (class "Default")
      (node (ref "8255-PPE") (pin "11") (pinfunction "PC6_11") (pintype "bidirectional"))
      (node (ref "PORT_C_H_IR") (pin "3") (pinfunction "3_3") (pintype "passive"))
    )
    (net (code "65") (name "/PC7") (class "Default")
      (node (ref "8255-PPE") (pin "10") (pinfunction "PC7_10") (pintype "bidirectional"))
      (node (ref "PORT_C_H_IR") (pin "4") (pinfunction "4_4") (pintype "passive"))
    )
    (net (code "66") (name "/RD*") (class "Default")
      (node (ref "8085-MPU") (pin "32") (pinfunction "RD_32") (pintype "output"))
      (node (ref "MEM-DEC") (pin "2") (pinfunction "B_2") (pintype "input"))
      (node (ref "P31-40") (pin "2") (pinfunction "2_2") (pintype "passive"))
    )
    (net (code "67") (name "/READY") (class "Default")
      (node (ref "8085-MPU") (pin "35") (pinfunction "READY_35") (pintype "input"))
      (node (ref "P31-40") (pin "5") (pinfunction "5_5") (pintype "passive"))
      (node (ref "R2") (pin "2") (pinfunction "2_2") (pintype "passive"))
    )
    (net (code "68") (name "/RES_IN") (class "Default")
      (node (ref "8085-MPU") (pin "36") (pinfunction "RES_IN_36") (pintype "input"))
      (node (ref "C29") (pin "1") (pinfunction "1_1") (pintype "passive"))
      (node (ref "C8") (pin "+") (pinfunction "+_+") (pintype "passive"))
      (node (ref "P31-40") (pin "6") (pinfunction "6_6") (pintype "passive"))
      (node (ref "R9") (pin "2") (pinfunction "2_2") (pintype "passive"))
      (node (ref "RESET") (pin "2") (pinfunction "S1_2") (pintype "passive"))
    )
    (net (code "69") (name "/RES_OUT") (class "Default")
      (node (ref "8085-MPU") (pin "3") (pinfunction "RES_OUT_3") (pintype "output"))
      (node (ref "8255-PPE") (pin "35") (pinfunction "RESET_35") (pintype "input"))
      (node (ref "P1-10") (pin "3") (pinfunction "3_3") (pintype "passive"))
    )
    (net (code "70") (name "/RST5_5") (class "Default")
      (node (ref "8085-MPU") (pin "9") (pinfunction "RST5_5_9") (pintype "input"))
      (node (ref "P1-10") (pin "9") (pinfunction "9_9") (pintype "passive"))
      (node (ref "R5") (pin "2") (pinfunction "2_2") (pintype "passive"))
    )
    (net (code "71") (name "/RST6_5") (class "Default")
      (node (ref "8085-MPU") (pin "8") (pinfunction "RST6_5_8") (pintype "input"))
      (node (ref "P1-10") (pin "8") (pinfunction "8_8") (pintype "passive"))
      (node (ref "R6") (pin "2") (pinfunction "2_2") (pintype "passive"))
    )
    (net (code "72") (name "/RST7_5") (class "Default")
      (node (ref "8085-MPU") (pin "7") (pinfunction "RST7_5_7") (pintype "input"))
      (node (ref "8254-COUNTER") (pin "11") (pinfunction "GATE0_11") (pintype "input"))
      (node (ref "8254-COUNTER") (pin "17") (pinfunction "OUT2_17") (pintype "output"))
      (node (ref "COUNTER0") (pin "3") (pinfunction "3_3") (pintype "passive"))
      (node (ref "COUNTER2") (pin "2") (pinfunction "2_2") (pintype "passive"))
      (node (ref "P1-10") (pin "7") (pinfunction "7_7") (pintype "passive"))
      (node (ref "R7") (pin "2") (pinfunction "2_2") (pintype "passive"))
    )
    (net (code "73") (name "/S0") (class "Default")
      (node (ref "8085-MPU") (pin "29") (pinfunction "S0_29") (pintype "output"))
      (node (ref "P21-30") (pin "9") (pinfunction "9_9") (pintype "passive"))
    )
    (net (code "74") (name "/S1") (class "Default")
      (node (ref "8085-MPU") (pin "33") (pinfunction "S1_33") (pintype "output"))
      (node (ref "P31-40") (pin "3") (pinfunction "3_3") (pintype "passive"))
    )
    (net (code "75") (name "/SENSOROUT") (class "Default")
      (node (ref "8254-COUNTER") (pin "9") (pinfunction "CLK0_9") (pintype "input"))
      (node (ref "COUNTER0") (pin "1") (pinfunction "1_1") (pintype "passive"))
      (node (ref "TCS0") (pin "2") (pinfunction "2_2") (pintype "passive"))
    )
    (net (code "76") (name "/SID") (class "Default")
      (node (ref "8085-MPU") (pin "5") (pinfunction "SID_5") (pintype "input"))
      (node (ref "C31") (pin "1") (pinfunction "1_1") (pintype "passive"))
      (node (ref "C9") (pin "+") (pinfunction "+_+") (pintype "passive"))
      (node (ref "P1-10") (pin "5") (pinfunction "5_5") (pintype "passive"))
      (node (ref "R10") (pin "2") (pinfunction "2_2") (pintype "passive"))
      (node (ref "SID") (pin "2") (pinfunction "S1_2") (pintype "passive"))
    )
    (net (code "77") (name "/SOD") (class "Default")
      (node (ref "8085-MPU") (pin "4") (pinfunction "SOD_4") (pintype "output"))
      (node (ref "P1-10") (pin "4") (pinfunction "4_4") (pintype "passive"))
      (node (ref "R15") (pin "2") (pinfunction "2_2") (pintype "passive"))
    )
    (net (code "78") (name "/TRAP") (class "Default")
      (node (ref "8085-MPU") (pin "6") (pinfunction "TRAP_6") (pintype "input"))
      (node (ref "P1-10") (pin "6") (pinfunction "6_6") (pintype "passive"))
      (node (ref "R8") (pin "2") (pinfunction "2_2") (pintype "passive"))
    )
    (net (code "79") (name "/WR*") (class "Default")
      (node (ref "8085-MPU") (pin "31") (pinfunction "WR_31") (pintype "output"))
      (node (ref "MEM-DEC") (pin "1") (pinfunction "A_1") (pintype "input"))
      (node (ref "P31-40") (pin "1") (pinfunction "1_1") (pintype "passive"))
    )
    (net (code "80") (name "/X1") (class "Default")
      (node (ref "8085-MPU") (pin "1") (pinfunction "X1_1") (pintype "input"))
      (node (ref "CRYSTAL") (pin "2") (pinfunction "2_2") (pintype "passive"))
      (node (ref "P1-10") (pin "1") (pinfunction "1_1") (pintype "passive"))
    )
    (net (code "81") (name "/X2") (class "Default")
      (node (ref "8085-MPU") (pin "2") (pinfunction "X2_2") (pintype "input"))
      (node (ref "C7") (pin "1") (pinfunction "1_1") (pintype "passive"))
      (node (ref "CRYSTAL") (pin "1") (pinfunction "1_1") (pintype "passive"))
      (node (ref "P1-10") (pin "2") (pinfunction "2_2") (pintype "passive"))
    )
    (net (code "82") (name "GND") (class "Default")
      (node (ref "8085-MPU") (pin "20") (pinfunction "VSS_20") (pintype "power_in"))
      (node (ref "8254-COUNTER") (pin "12") (pinfunction "GND_12") (pintype "power_in"))
      (node (ref "8255-PPE") (pin "7") (pinfunction "GND_7") (pintype "power_in"))
      (node (ref "ADDLATCH") (pin "1") (pinfunction "OC_1") (pintype "input"))
      (node (ref "ADDLATCH") (pin "10") (pinfunction "GND_10") (pintype "power_in"))
      (node (ref "C16") (pin "2") (pinfunction "2_2") (pintype "passive"))
      (node (ref "C17") (pin "-") (pinfunction "-_-") (pintype "passive"))
      (node (ref "C18") (pin "2") (pinfunction "2_2") (pintype "passive"))
      (node (ref "C19") (pin "2") (pinfunction "2_2") (pintype "passive"))
      (node (ref "C20") (pin "2") (pinfunction "2_2") (pintype "passive"))
      (node (ref "C24") (pin "2") (pinfunction "2_2") (pintype "passive"))
      (node (ref "C25") (pin "2") (pinfunction "2_2") (pintype "passive"))
      (node (ref "C26") (pin "2") (pinfunction "2_2") (pintype "passive"))
      (node (ref "C27") (pin "2") (pinfunction "2_2") (pintype "passive"))
      (node (ref "C29") (pin "2") (pinfunction "2_2") (pintype "passive"))
      (node (ref "C31") (pin "2") (pinfunction "2_2") (pintype "passive"))
      (node (ref "C33") (pin "2") (pinfunction "2_2") (pintype "passive"))
      (node (ref "C7") (pin "2") (pinfunction "2_2") (pintype "passive"))
      (node (ref "C8") (pin "-") (pinfunction "-_-") (pintype "passive"))
      (node (ref "C9") (pin "-") (pinfunction "-_-") (pintype "passive"))
      (node (ref "IC1") (pin "7") (pinfunction "GND_7") (pintype "power_in"))
      (node (ref "MEM-DEC") (pin "4") (pinfunction "G2A_4") (pintype "input"))
      (node (ref "MEM-DEC") (pin "5") (pinfunction "G2B_5") (pintype "input"))
      (node (ref "MEM-DEC") (pin "8") (pinfunction "GND_8") (pintype "power_in"))
      (node (ref "P11-20") (pin "10") (pinfunction "10_10") (pintype "passive"))
      (node (ref "PWR") (pin "K") (pinfunction "C_K") (pintype "passive"))
      (node (ref "PWR5") (pin "2") (pinfunction "2_2") (pintype "passive"))
      (node (ref "R3") (pin "1") (pinfunction "1_1") (pintype "passive"))
      (node (ref "R4") (pin "1") (pinfunction "1_1") (pintype "passive"))
      (node (ref "R5") (pin "1") (pinfunction "1_1") (pintype "passive"))
      (node (ref "R6") (pin "1") (pinfunction "1_1") (pintype "passive"))
      (node (ref "R7") (pin "1") (pinfunction "1_1") (pintype "passive"))
      (node (ref "R8") (pin "1") (pinfunction "1_1") (pintype "passive"))
      (node (ref "RAM-62256P") (pin "14") (pinfunction "VSS_14") (pintype "power_in"))
      (node (ref "RESET") (pin "4") (pinfunction "P1_4") (pintype "passive"))
      (node (ref "ROM-58C256") (pin "14") (pinfunction "VSS_14") (pintype "power_in"))
      (node (ref "SID") (pin "4") (pinfunction "P1_4") (pintype "passive"))
      (node (ref "SOD") (pin "K") (pinfunction "C_K") (pintype "passive"))
      (node (ref "TCS0") (pin "3") (pinfunction "3_3") (pintype "passive"))
      (node (ref "TCS0") (pin "4") (pinfunction "4_4") (pintype "passive"))
      (node (ref "USB") (pin "GND") (pinfunction "GND_GND") (pintype "power_in"))
    )
    (net (code "83") (name "Net-(PWR-PadA)") (class "Default")
      (node (ref "PWR") (pin "A") (pinfunction "A_A") (pintype "passive"))
      (node (ref "R14") (pin "2") (pinfunction "2_2") (pintype "passive"))
    )
    (net (code "84") (name "Net-(R15-Pad1)") (class "Default")
      (node (ref "R15") (pin "1") (pinfunction "1_1") (pintype "passive"))
      (node (ref "SOD") (pin "A") (pinfunction "A_A") (pintype "passive"))
    )
    (net (code "85") (name "VCC") (class "Default")
      (node (ref "8085-MPU") (pin "40") (pinfunction "VCC_40") (pintype "power_in"))
      (node (ref "8254-COUNTER") (pin "24") (pinfunction "VCC_24") (pintype "power_in"))
      (node (ref "8255-PPE") (pin "26") (pinfunction "VCC_26") (pintype "power_in"))
      (node (ref "ADDLATCH") (pin "20") (pinfunction "VCC_20") (pintype "power_in"))
      (node (ref "C16") (pin "1") (pinfunction "1_1") (pintype "passive"))
      (node (ref "C17") (pin "+") (pinfunction "+_+") (pintype "passive"))
      (node (ref "C18") (pin "1") (pinfunction "1_1") (pintype "passive"))
      (node (ref "C19") (pin "1") (pinfunction "1_1") (pintype "passive"))
      (node (ref "C20") (pin "1") (pinfunction "1_1") (pintype "passive"))
      (node (ref "C24") (pin "1") (pinfunction "1_1") (pintype "passive"))
      (node (ref "C25") (pin "1") (pinfunction "1_1") (pintype "passive"))
      (node (ref "C26") (pin "1") (pinfunction "1_1") (pintype "passive"))
      (node (ref "C27") (pin "1") (pinfunction "1_1") (pintype "passive"))
      (node (ref "C33") (pin "1") (pinfunction "1_1") (pintype "passive"))
      (node (ref "IC1") (pin "14") (pinfunction "VCC_14") (pintype "power_in"))
      (node (ref "MEM-DEC") (pin "16") (pinfunction "VCC_16") (pintype "power_in"))
      (node (ref "MEM-DEC") (pin "6") (pinfunction "G1_6") (pintype "input"))
      (node (ref "P31-40") (pin "10") (pinfunction "10_10") (pintype "passive"))
      (node (ref "PWR5") (pin "1") (pinfunction "1_1") (pintype "passive"))
      (node (ref "R10") (pin "1") (pinfunction "1_1") (pintype "passive"))
      (node (ref "R12") (pin "2") (pinfunction "2_2") (pintype "passive"))
      (node (ref "R13") (pin "2") (pinfunction "2_2") (pintype "passive"))
      (node (ref "R14") (pin "1") (pinfunction "1_1") (pintype "passive"))
      (node (ref "R2") (pin "1") (pinfunction "1_1") (pintype "passive"))
      (node (ref "R9") (pin "1") (pinfunction "1_1") (pintype "passive"))
      (node (ref "RAM-62256P") (pin "28") (pinfunction "VCC_28") (pintype "power_in"))
      (node (ref "ROM-58C256") (pin "27") (pinfunction "~{WE}_27") (pintype "input"))
      (node (ref "ROM-58C256") (pin "28") (pinfunction "VCC_28") (pintype "power_in"))
      (node (ref "TCS0") (pin "1") (pinfunction "1_1") (pintype "passive"))
      (node (ref "USB") (pin "VBUS") (pinfunction "VCC_VBUS") (pintype "power_in"))
    )
    (net (code "86") (name "unconnected-(MEM-DECA-Y0-Pad15)") (class "Default")
      (node (ref "MEM-DEC") (pin "15") (pinfunction "Y0_15") (pintype "output"))
    )
    (net (code "87") (name "unconnected-(MEM-DECA-Y3-Pad12)") (class "Default")
      (node (ref "MEM-DEC") (pin "12") (pinfunction "Y3_12") (pintype "output"))
    )
    (net (code "88") (name "unconnected-(MEM-DECA-Y4-Pad11)") (class "Default")
      (node (ref "MEM-DEC") (pin "11") (pinfunction "Y4_11") (pintype "output"))
    )
    (net (code "89") (name "unconnected-(MEM-DECA-Y7-Pad7)") (class "Default")
      (node (ref "MEM-DEC") (pin "7") (pinfunction "Y7_7") (pintype "output"))
    )
    (net (code "90") (name "unconnected-(RESET-P-Pad3)") (class "Default")
      (node (ref "RESET") (pin "3") (pinfunction "P_3") (pintype "passive"))
    )
    (net (code "91") (name "unconnected-(RESET-S-Pad1)") (class "Default")
      (node (ref "RESET") (pin "1") (pinfunction "S_1") (pintype "passive"))
    )
    (net (code "92") (name "unconnected-(SID-P-Pad3)") (class "Default")
      (node (ref "SID") (pin "3") (pinfunction "P_3") (pintype "passive"))
    )
    (net (code "93") (name "unconnected-(SID-S-Pad1)") (class "Default")
      (node (ref "SID") (pin "1") (pinfunction "S_1") (pintype "passive"))
    )
  )
)
